# Adafruit_BNO055.net
KiCad netlist of a schematic drawn in EAGLE
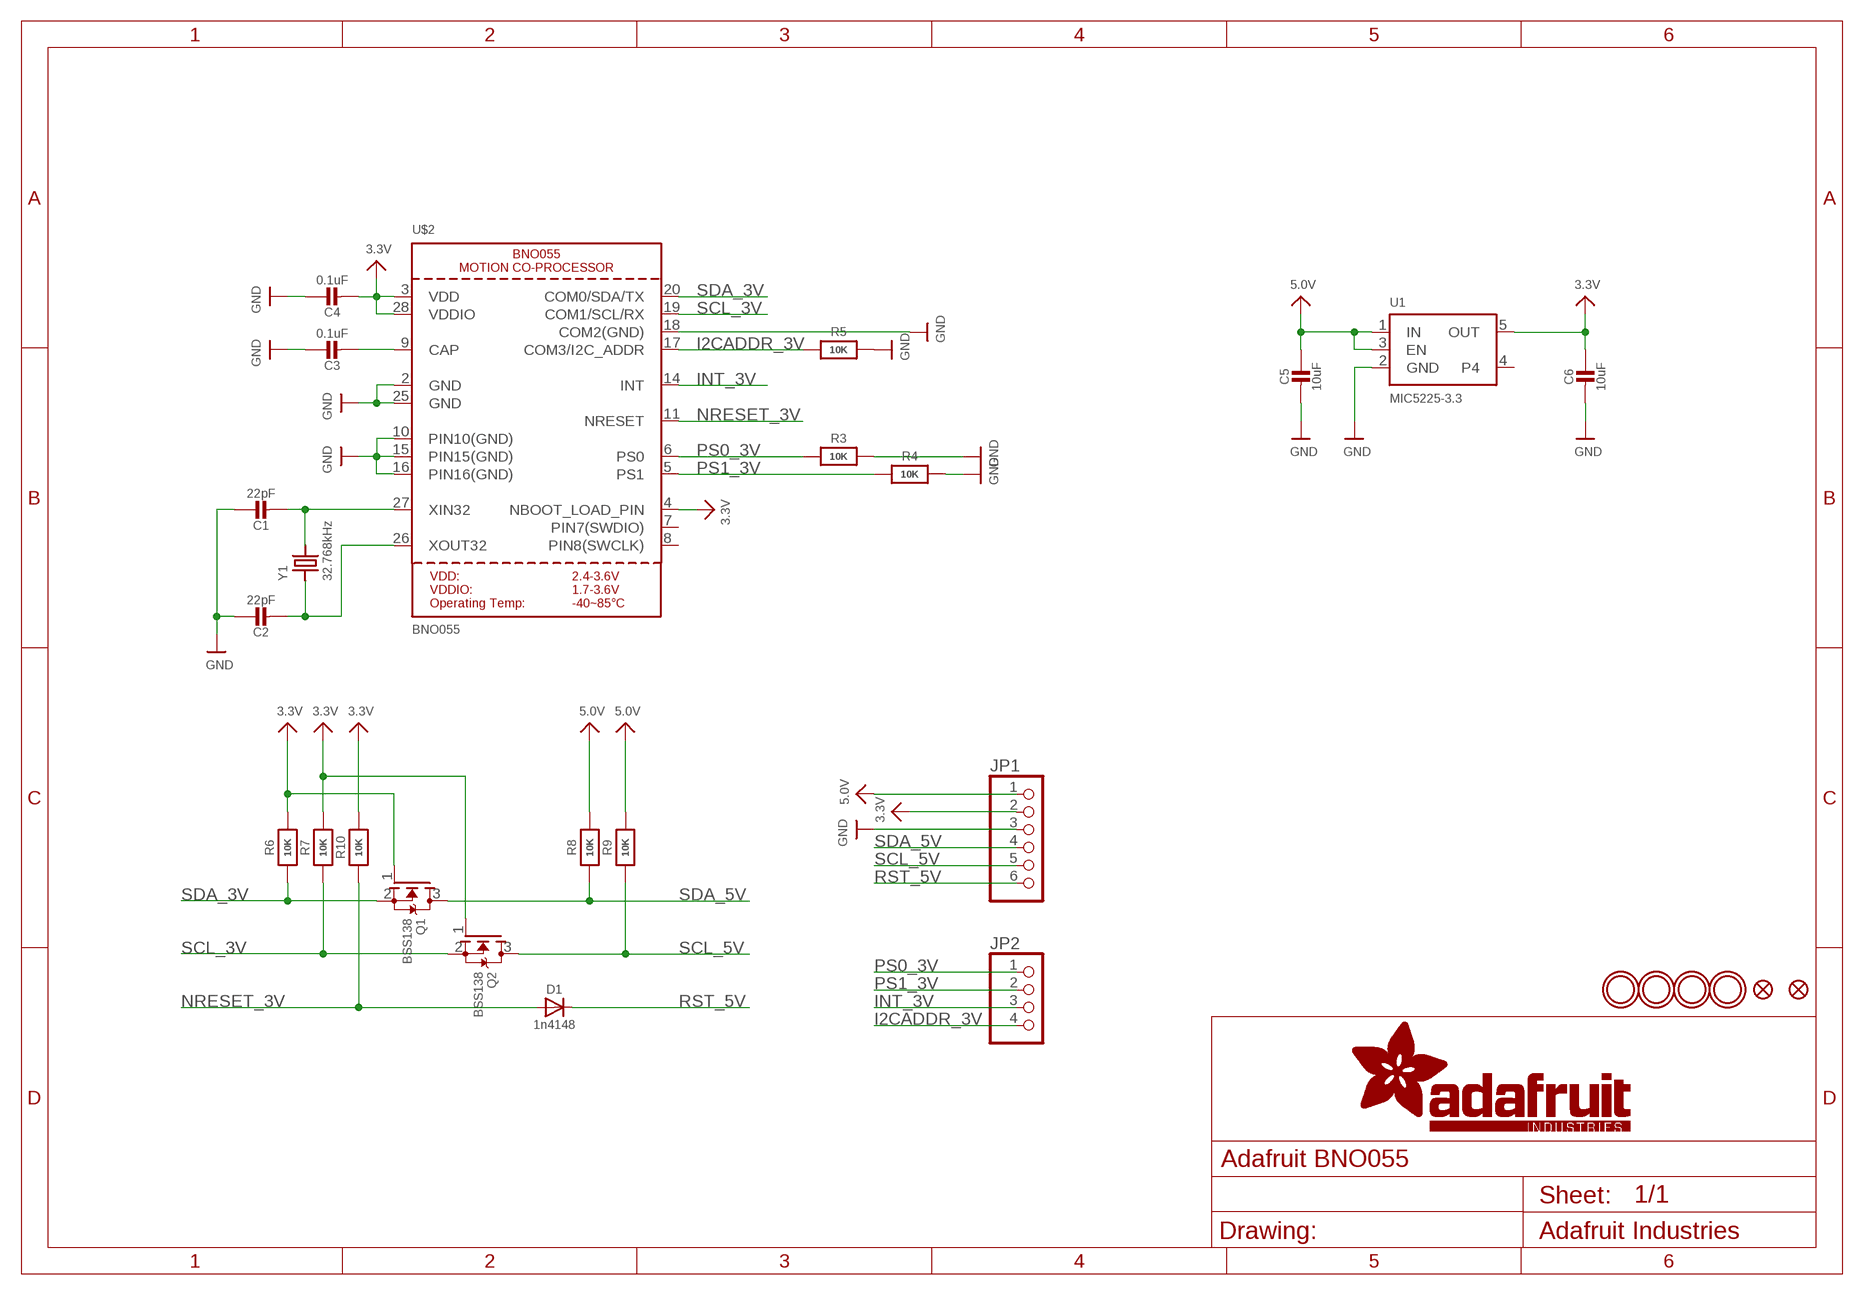
[diagram p0: schematic, sheet 1]

(export (version "E")
  (design (tool "Eeschema 10.0.6"))
  (components
    (comp (ref "C1")
      (value "22pF")
      (footprint "eagle-import:0805-NO")
      (libsource (lib "eagle-import") (part "CAP_CERAMIC0805-NOOUTLINE"))
    )
    (comp (ref "C2")
      (value "22pF")
      (footprint "eagle-import:0805-NO")
      (libsource (lib "eagle-import") (part "CAP_CERAMIC0805-NOOUTLINE"))
    )
    (comp (ref "C3")
      (value "0.1uF")
      (footprint "eagle-import:0805-NO")
      (libsource (lib "eagle-import") (part "CAP_CERAMIC0805-NOOUTLINE"))
    )
    (comp (ref "C4")
      (value "0.1uF")
      (footprint "eagle-import:0805_10MGAP")
      (libsource (lib "eagle-import") (part "CAP_CERAMIC0805_10MGAP"))
    )
    (comp (ref "C5")
      (value "10uF")
      (footprint "eagle-import:0805-NO")
      (libsource (lib "eagle-import") (part "CAP_CERAMIC0805-NOOUTLINE"))
    )
    (comp (ref "C6")
      (value "10uF")
      (footprint "eagle-import:0805_10MGAP")
      (libsource (lib "eagle-import") (part "CAP_CERAMIC0805_10MGAP"))
    )
    (comp (ref "D1")
      (value "1n4148")
      (footprint "eagle-import:SOD-323")
      (libsource (lib "eagle-import") (part "DIODESOD-323"))
    )
    (comp (ref "FID1")
      (value "FIDUCIAL\"\"")
      (footprint "eagle-import:FIDUCIAL_1MM")
      (libsource (lib "eagle-import") (part "FIDUCIAL{dblquote}{dblquote}"))
    )
    (comp (ref "FID2")
      (value "FIDUCIAL\"\"")
      (footprint "eagle-import:FIDUCIAL_1MM")
      (libsource (lib "eagle-import") (part "FIDUCIAL{dblquote}{dblquote}"))
    )
    (comp (ref "JP1")
      (value "HEADER-1X676MIL")
      (footprint "eagle-import:1X06_ROUND_76")
      (libsource (lib "eagle-import") (part "HEADER-1X676MIL"))
    )
    (comp (ref "JP2")
      (value "HEADER-1X476MIL")
      (footprint "eagle-import:1X04_ROUND_76")
      (libsource (lib "eagle-import") (part "HEADER-1X476MIL"))
    )
    (comp (ref "Q1")
      (value "BSS138")
      (footprint "eagle-import:SOT23-WIDE")
      (libsource (lib "eagle-import") (part "MOSFET-NWIDE"))
    )
    (comp (ref "Q2")
      (value "BSS138")
      (footprint "eagle-import:SOT23-WIDE")
      (libsource (lib "eagle-import") (part "MOSFET-NWIDE"))
    )
    (comp (ref "R3")
      (value "10K")
      (footprint "eagle-import:0805-NO")
      (libsource (lib "eagle-import") (part "RESISTOR0805_NOOUTLINE"))
    )
    (comp (ref "R4")
      (value "10K")
      (footprint "eagle-import:0805-NO")
      (libsource (lib "eagle-import") (part "RESISTOR0805_NOOUTLINE"))
    )
    (comp (ref "R5")
      (value "10K")
      (footprint "eagle-import:0805-NO")
      (libsource (lib "eagle-import") (part "RESISTOR0805_NOOUTLINE"))
    )
    (comp (ref "R6")
      (value "10K")
      (footprint "eagle-import:0805-NO")
      (libsource (lib "eagle-import") (part "RESISTOR0805_NOOUTLINE"))
    )
    (comp (ref "R7")
      (value "10K")
      (footprint "eagle-import:0805-NO")
      (libsource (lib "eagle-import") (part "RESISTOR0805_NOOUTLINE"))
    )
    (comp (ref "R8")
      (value "10K")
      (footprint "eagle-import:_0805MP")
      (libsource (lib "eagle-import") (part "RESISTOR_0805MP"))
    )
    (comp (ref "R9")
      (value "10K")
      (footprint "eagle-import:_0805MP")
      (libsource (lib "eagle-import") (part "RESISTOR_0805MP"))
    )
    (comp (ref "R10")
      (value "10K")
      (footprint "eagle-import:0805-NO")
      (libsource (lib "eagle-import") (part "RESISTOR0805_NOOUTLINE"))
    )
    (comp (ref "U$2")
      (value "BNO055")
      (footprint "eagle-import:BNO055")
      (libsource (lib "eagle-import") (part "BNO055"))
    )
    (comp (ref "U$29")
      (value "MOUNTINGHOLE2.5_THICK")
      (footprint "eagle-import:MOUNTINGHOLE_2.5_PLATED_THICK")
      (libsource (lib "eagle-import") (part "MOUNTINGHOLE2.5_THICK"))
    )
    (comp (ref "U$30")
      (value "MOUNTINGHOLE2.5_THICK")
      (footprint "eagle-import:MOUNTINGHOLE_2.5_PLATED_THICK")
      (libsource (lib "eagle-import") (part "MOUNTINGHOLE2.5_THICK"))
    )
    (comp (ref "U$31")
      (value "MOUNTINGHOLE2.5_THICK")
      (footprint "eagle-import:MOUNTINGHOLE_2.5_PLATED_THICK")
      (libsource (lib "eagle-import") (part "MOUNTINGHOLE2.5_THICK"))
    )
    (comp (ref "U$32")
      (value "MOUNTINGHOLE2.5_THICK")
      (footprint "eagle-import:MOUNTINGHOLE_2.5_PLATED_THICK")
      (libsource (lib "eagle-import") (part "MOUNTINGHOLE2.5_THICK"))
    )
    (comp (ref "U1")
      (value "MIC5225-3.3")
      (footprint "eagle-import:SOT23-5")
      (libsource (lib "eagle-import") (part "VREG_SOT23-5"))
    )
    (comp (ref "Y1")
      (value "32.768kHz")
      (footprint "eagle-import:CRYSTAL_8X3.8")
      (libsource (lib "eagle-import") (part "CRYSTAL8.0X3.8"))
    )
  )
  (nets
    (net (code "1") (name "/I2CADDR_3V") (class "Default")
      (node (ref "JP2") (pin "4") (pinfunction "4_4") (pintype "passive"))
      (node (ref "R5") (pin "1") (pinfunction "1_1") (pintype "passive"))
      (node (ref "U$2") (pin "17") (pinfunction "COM3/I2C_ADDR_17") (pintype "bidirectional"))
    )
    (net (code "2") (name "/INT_3V") (class "Default")
      (node (ref "JP2") (pin "3") (pinfunction "3_3") (pintype "passive"))
      (node (ref "U$2") (pin "14") (pinfunction "INT_14") (pintype "output"))
    )
    (net (code "3") (name "/NRESET_3V") (class "Default")
      (node (ref "D1") (pin "A") (pinfunction "A_A") (pintype "passive"))
      (node (ref "R10") (pin "1") (pinfunction "1_1") (pintype "passive"))
      (node (ref "U$2") (pin "11") (pinfunction "NRESET_11") (pintype "bidirectional"))
    )
    (net (code "4") (name "/PS0_3V") (class "Default")
      (node (ref "JP2") (pin "1") (pinfunction "1_1") (pintype "passive"))
      (node (ref "R3") (pin "1") (pinfunction "1_1") (pintype "passive"))
      (node (ref "U$2") (pin "6") (pinfunction "PS0_6") (pintype "input"))
    )
    (net (code "5") (name "/PS1_3V") (class "Default")
      (node (ref "JP2") (pin "2") (pinfunction "2_2") (pintype "passive"))
      (node (ref "R4") (pin "1") (pinfunction "1_1") (pintype "passive"))
      (node (ref "U$2") (pin "5") (pinfunction "PS1_5") (pintype "input"))
    )
    (net (code "6") (name "/RST_5V") (class "Default")
      (node (ref "D1") (pin "C") (pinfunction "C_C") (pintype "passive"))
      (node (ref "JP1") (pin "6") (pinfunction "6_6") (pintype "passive"))
    )
    (net (code "7") (name "/SCL_3V") (class "Default")
      (node (ref "Q2") (pin "2") (pinfunction "S_2") (pintype "bidirectional"))
      (node (ref "R7") (pin "1") (pinfunction "1_1") (pintype "passive"))
      (node (ref "U$2") (pin "19") (pinfunction "COM1/SCL/RX_19") (pintype "bidirectional"))
    )
    (net (code "8") (name "/SCL_5V") (class "Default")
      (node (ref "JP1") (pin "5") (pinfunction "5_5") (pintype "passive"))
      (node (ref "Q2") (pin "3") (pinfunction "D_3") (pintype "bidirectional"))
      (node (ref "R9") (pin "1") (pinfunction "1_1") (pintype "passive"))
    )
    (net (code "9") (name "/SDA_3V") (class "Default")
      (node (ref "Q1") (pin "2") (pinfunction "S_2") (pintype "bidirectional"))
      (node (ref "R6") (pin "1") (pinfunction "1_1") (pintype "passive"))
      (node (ref "U$2") (pin "20") (pinfunction "COM0/SDA/TX_20") (pintype "bidirectional"))
    )
    (net (code "10") (name "/SDA_5V") (class "Default")
      (node (ref "JP1") (pin "4") (pinfunction "4_4") (pintype "passive"))
      (node (ref "Q1") (pin "3") (pinfunction "D_3") (pintype "bidirectional"))
      (node (ref "R8") (pin "1") (pinfunction "1_1") (pintype "passive"))
    )
    (net (code "11") (name "3.3V") (class "Default")
      (node (ref "C4") (pin "2") (pinfunction "2_2") (pintype "passive"))
      (node (ref "C6") (pin "1") (pinfunction "1_1") (pintype "passive"))
      (node (ref "JP1") (pin "2") (pinfunction "2_2") (pintype "passive"))
      (node (ref "Q1") (pin "1") (pinfunction "G_1") (pintype "bidirectional"))
      (node (ref "Q2") (pin "1") (pinfunction "G_1") (pintype "bidirectional"))
      (node (ref "R10") (pin "2") (pinfunction "2_2") (pintype "passive"))
      (node (ref "R6") (pin "2") (pinfunction "2_2") (pintype "passive"))
      (node (ref "R7") (pin "2") (pinfunction "2_2") (pintype "passive"))
      (node (ref "U$2") (pin "28") (pinfunction "VDDIO_28") (pintype "power_in"))
      (node (ref "U$2") (pin "3") (pinfunction "VDD_3") (pintype "power_in"))
      (node (ref "U$2") (pin "4") (pinfunction "NBOOT_LOAD_PIN_4") (pintype "bidirectional"))
      (node (ref "U1") (pin "5") (pinfunction "OUT_5") (pintype "power_in"))
    )
    (net (code "12") (name "5.0V") (class "Default")
      (node (ref "C5") (pin "1") (pinfunction "1_1") (pintype "passive"))
      (node (ref "JP1") (pin "1") (pinfunction "1_1") (pintype "passive"))
      (node (ref "R8") (pin "2") (pinfunction "2_2") (pintype "passive"))
      (node (ref "R9") (pin "2") (pinfunction "2_2") (pintype "passive"))
      (node (ref "U1") (pin "1") (pinfunction "IN_1") (pintype "power_in"))
      (node (ref "U1") (pin "3") (pinfunction "EN_3") (pintype "input"))
    )
    (net (code "13") (name "GND") (class "Default")
      (node (ref "C1") (pin "1") (pinfunction "1_1") (pintype "passive"))
      (node (ref "C2") (pin "1") (pinfunction "1_1") (pintype "passive"))
      (node (ref "C3") (pin "1") (pinfunction "1_1") (pintype "passive"))
      (node (ref "C4") (pin "1") (pinfunction "1_1") (pintype "passive"))
      (node (ref "C5") (pin "2") (pinfunction "2_2") (pintype "passive"))
      (node (ref "C6") (pin "2") (pinfunction "2_2") (pintype "passive"))
      (node (ref "JP1") (pin "3") (pinfunction "3_3") (pintype "passive"))
      (node (ref "R3") (pin "2") (pinfunction "2_2") (pintype "passive"))
      (node (ref "R4") (pin "2") (pinfunction "2_2") (pintype "passive"))
      (node (ref "R5") (pin "2") (pinfunction "2_2") (pintype "passive"))
      (node (ref "U$2") (pin "10") (pinfunction "PIN10(GND)_10") (pintype "bidirectional"))
      (node (ref "U$2") (pin "15") (pinfunction "PIN15(GND)_15") (pintype "bidirectional"))
      (node (ref "U$2") (pin "16") (pinfunction "PIN16(GND)_16") (pintype "bidirectional"))
      (node (ref "U$2") (pin "18") (pinfunction "COM2(GND)_18") (pintype "bidirectional"))
      (node (ref "U$2") (pin "2") (pinfunction "GND_2") (pintype "power_in"))
      (node (ref "U$2") (pin "25") (pinfunction "GND_25") (pintype "power_in"))
      (node (ref "U1") (pin "2") (pinfunction "GND_2") (pintype "power_in"))
    )
    (net (code "14") (name "Net-(U$2-CAP)") (class "Default")
      (node (ref "C3") (pin "2") (pinfunction "2_2") (pintype "passive"))
      (node (ref "U$2") (pin "9") (pinfunction "CAP_9") (pintype "passive"))
    )
    (net (code "15") (name "Net-(U$2-XIN32)") (class "Default")
      (node (ref "C1") (pin "2") (pinfunction "2_2") (pintype "passive"))
      (node (ref "U$2") (pin "27") (pinfunction "XIN32_27") (pintype "input"))
      (node (ref "Y1") (pin "P$4") (pinfunction "2_P$4") (pintype "passive"))
    )
    (net (code "16") (name "Net-(U$2-XOUT32)") (class "Default")
      (node (ref "C2") (pin "2") (pinfunction "2_2") (pintype "passive"))
      (node (ref "U$2") (pin "26") (pinfunction "XOUT32_26") (pintype "output"))
      (node (ref "Y1") (pin "P$1") (pinfunction "1_P$1") (pintype "passive"))
    )
    (net (code "17") (name "unconnected-(U$2-PIN7(SWDIO)-Pad7)") (class "Default")
      (node (ref "U$2") (pin "7") (pinfunction "PIN7(SWDIO)_7") (pintype "bidirectional"))
    )
    (net (code "18") (name "unconnected-(U$2-PIN8(SWCLK)-Pad8)") (class "Default")
      (node (ref "U$2") (pin "8") (pinfunction "PIN8(SWCLK)_8") (pintype "bidirectional"))
    )
    (net (code "19") (name "unconnected-(U1-P4-Pad4)") (class "Default")
      (node (ref "U1") (pin "4") (pinfunction "P4_4") (pintype "bidirectional"))
    )
  )
)
